# Teensy_PCB.net
KiCad netlist of a schematic drawn in EAGLE
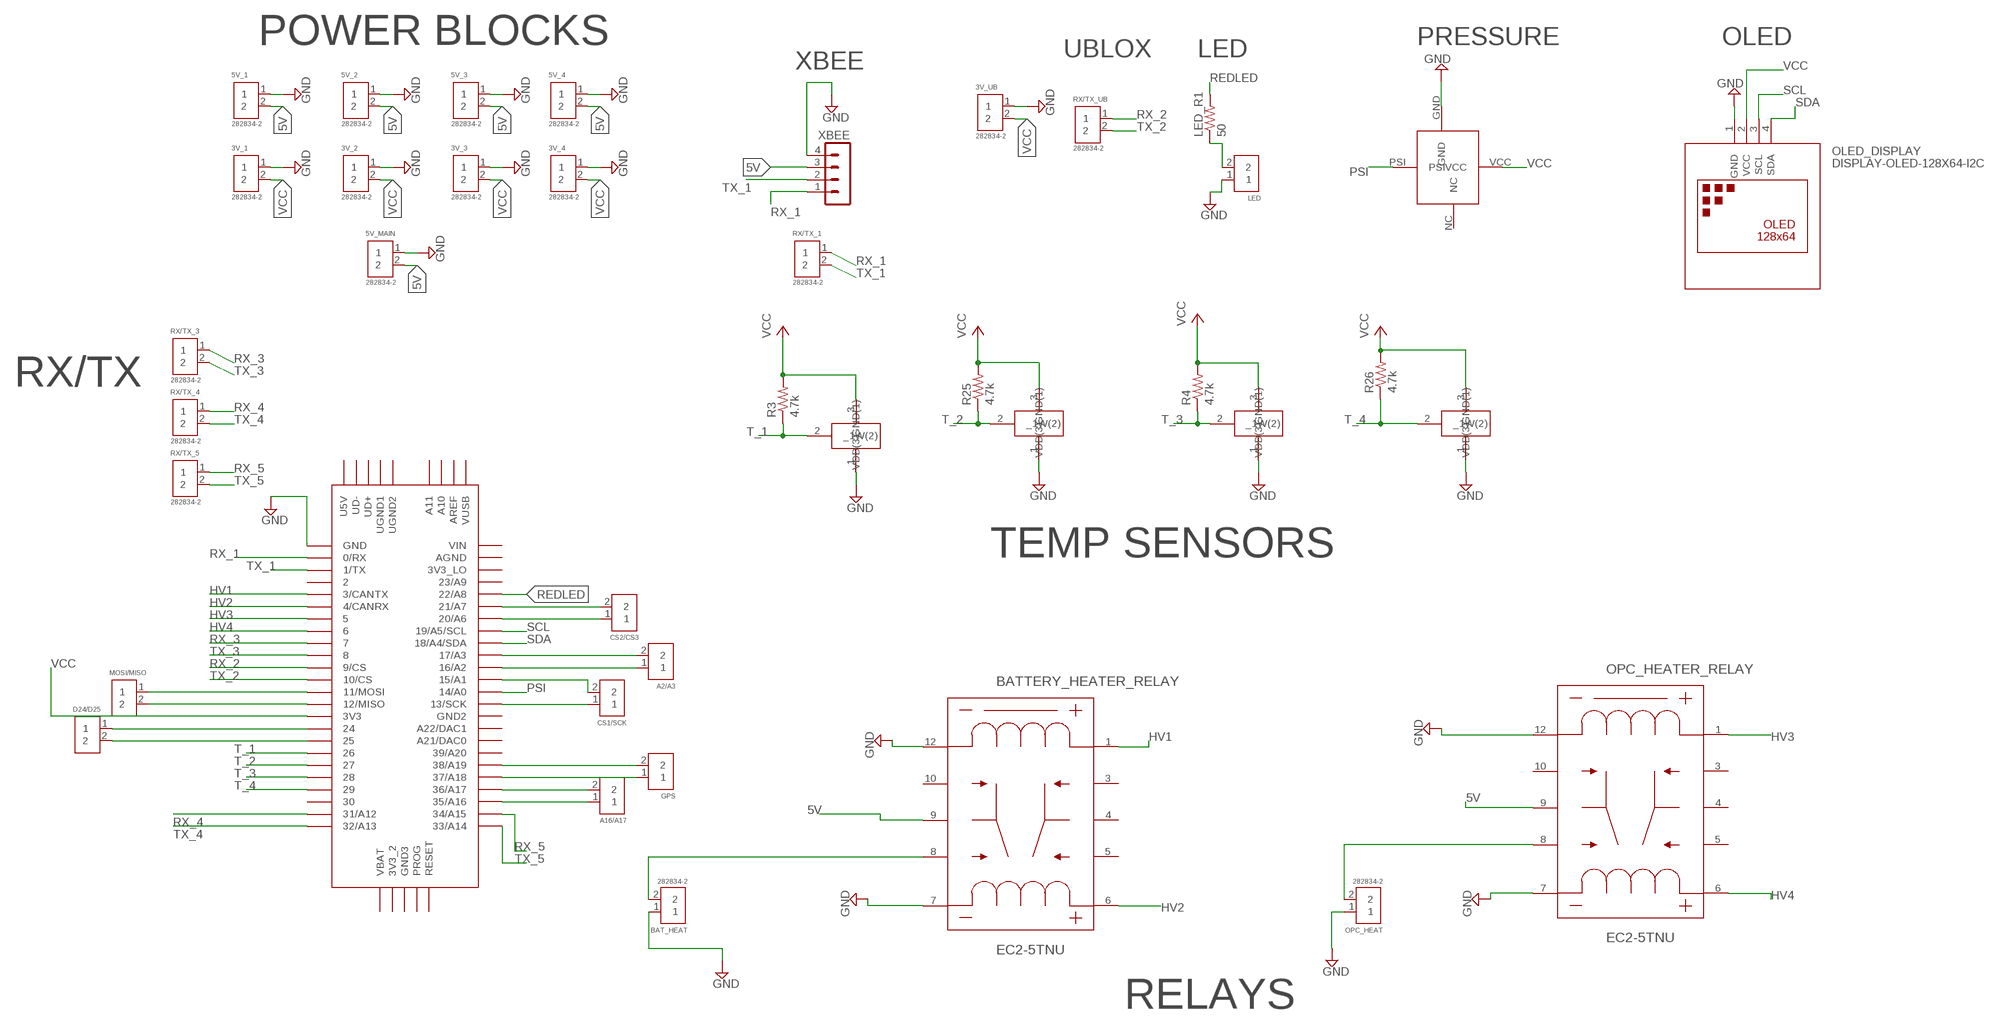
[diagram p0: schematic, sheet 1]

(export (version "E")
  (design (tool "Eeschema 10.0.6"))
  (components
    (comp (ref "3V_1")
      (value "282834-2")
      (footprint "eagle-import:CONN_282834-2")
      (fields (field (name "DIGI-KEY_PART_NUMBER") "A98333-ND") (field (name "MF") "TE Connectivity"))
      (libsource (lib "eagle-import") (part "282834-2"))
    )
    (comp (ref "3V_2")
      (value "282834-2")
      (footprint "eagle-import:CONN_282834-2")
      (fields (field (name "DIGI-KEY_PART_NUMBER") "A98333-ND") (field (name "MF") "TE Connectivity"))
      (libsource (lib "eagle-import") (part "282834-2"))
    )
    (comp (ref "3V_3")
      (value "282834-2")
      (footprint "eagle-import:CONN_282834-2")
      (fields (field (name "DIGI-KEY_PART_NUMBER") "A98333-ND") (field (name "MF") "TE Connectivity"))
      (libsource (lib "eagle-import") (part "282834-2"))
    )
    (comp (ref "3V_4")
      (value "282834-2")
      (footprint "eagle-import:CONN_282834-2")
      (fields (field (name "DIGI-KEY_PART_NUMBER") "A98333-ND") (field (name "MF") "TE Connectivity"))
      (libsource (lib "eagle-import") (part "282834-2"))
    )
    (comp (ref "3V_UB")
      (value "282834-2")
      (footprint "eagle-import:CONN_282834-2")
      (fields (field (name "DIGI-KEY_PART_NUMBER") "A98333-ND") (field (name "MF") "TE Connectivity"))
      (libsource (lib "eagle-import") (part "282834-2"))
    )
    (comp (ref "5V_1")
      (value "282834-2")
      (footprint "eagle-import:CONN_282834-2")
      (fields (field (name "DIGI-KEY_PART_NUMBER") "A98333-ND") (field (name "MF") "TE Connectivity"))
      (libsource (lib "eagle-import") (part "282834-2"))
    )
    (comp (ref "5V_2")
      (value "282834-2")
      (footprint "eagle-import:CONN_282834-2")
      (fields (field (name "DIGI-KEY_PART_NUMBER") "A98333-ND") (field (name "MF") "TE Connectivity"))
      (libsource (lib "eagle-import") (part "282834-2"))
    )
    (comp (ref "5V_3")
      (value "282834-2")
      (footprint "eagle-import:CONN_282834-2")
      (fields (field (name "DIGI-KEY_PART_NUMBER") "A98333-ND") (field (name "MF") "TE Connectivity"))
      (libsource (lib "eagle-import") (part "282834-2"))
    )
    (comp (ref "5V_4")
      (value "282834-2")
      (footprint "eagle-import:CONN_282834-2")
      (fields (field (name "DIGI-KEY_PART_NUMBER") "A98333-ND") (field (name "MF") "TE Connectivity"))
      (libsource (lib "eagle-import") (part "282834-2"))
    )
    (comp (ref "5V_MAIN")
      (value "282834-2")
      (footprint "eagle-import:CONN_282834-2")
      (fields (field (name "DIGI-KEY_PART_NUMBER") "A98333-ND") (field (name "MF") "TE Connectivity"))
      (libsource (lib "eagle-import") (part "282834-2"))
    )
    (comp (ref "A2/A3")
      (value "282834-2")
      (footprint "eagle-import:CONN_282834-2")
      (fields (field (name "DIGI-KEY_PART_NUMBER") "A98333-ND") (field (name "MF") "TE Connectivity"))
      (libsource (lib "eagle-import") (part "282834-2"))
    )
    (comp (ref "A16/A17")
      (value "282834-2")
      (footprint "eagle-import:CONN_282834-2")
      (fields (field (name "DIGI-KEY_PART_NUMBER") "A98333-ND") (field (name "MF") "TE Connectivity"))
      (libsource (lib "eagle-import") (part "282834-2"))
    )
    (comp (ref "BATTERY_HEATER_RELAY")
      (value "EC2-5TNU")
      (footprint "eagle-import:EC2TNU")
      (fields (field (name "MANUFACTURER_PART_NUMBER") "EC25TNU"))
      (libsource (lib "eagle-import") (part "EC2-5TNU"))
    )
    (comp (ref "BAT_HEAT")
      (value "282834-2")
      (footprint "eagle-import:CONN_282834-2")
      (fields (field (name "DIGI-KEY_PART_NUMBER") "A98333-ND") (field (name "MF") "TE Connectivity"))
      (libsource (lib "eagle-import") (part "282834-2"))
    )
    (comp (ref "CS1/SCK")
      (value "282834-2")
      (footprint "eagle-import:CONN_282834-2")
      (fields (field (name "DIGI-KEY_PART_NUMBER") "A98333-ND") (field (name "MF") "TE Connectivity"))
      (libsource (lib "eagle-import") (part "282834-2"))
    )
    (comp (ref "CS2/CS3")
      (value "282834-2")
      (footprint "eagle-import:CONN_282834-2")
      (fields (field (name "DIGI-KEY_PART_NUMBER") "A98333-ND") (field (name "MF") "TE Connectivity"))
      (libsource (lib "eagle-import") (part "282834-2"))
    )
    (comp (ref "D24/D25")
      (value "282834-2")
      (footprint "eagle-import:CONN_282834-2")
      (fields (field (name "DIGI-KEY_PART_NUMBER") "A98333-ND") (field (name "MF") "TE Connectivity"))
      (libsource (lib "eagle-import") (part "282834-2"))
    )
    (comp (ref "GPS")
      (value "282834-2")
      (footprint "eagle-import:CONN_282834-2")
      (fields (field (name "DIGI-KEY_PART_NUMBER") "A98333-ND") (field (name "MF") "TE Connectivity"))
      (libsource (lib "eagle-import") (part "282834-2"))
    )
    (comp (ref "LED")
      (value "282834-2")
      (footprint "eagle-import:CONN_282834-2")
      (fields (field (name "DIGI-KEY_PART_NUMBER") "A98333-ND") (field (name "MF") "TE Connectivity"))
      (libsource (lib "eagle-import") (part "282834-2"))
    )
    (comp (ref "LED_R1")
      (value "50")
      (footprint "eagle-import:0204_7")
      (libsource (lib "eagle-import") (part "R-US_0204/7"))
    )
    (comp (ref "MOSI/MISO")
      (value "282834-2")
      (footprint "eagle-import:CONN_282834-2")
      (fields (field (name "DIGI-KEY_PART_NUMBER") "A98333-ND") (field (name "MF") "TE Connectivity"))
      (libsource (lib "eagle-import") (part "282834-2"))
    )
    (comp (ref "OLED_DISPLAY")
      (value "DISPLAY-OLED-128X64-I2C")
      (footprint "eagle-import:DISPLAY-OLED-128X64-I2C")
      (libsource (lib "eagle-import") (part "DISPLAY-OLED-128X64-I2C"))
    )
    (comp (ref "OPC_HEAT")
      (value "282834-2")
      (footprint "eagle-import:CONN_282834-2")
      (fields (field (name "DIGI-KEY_PART_NUMBER") "A98333-ND") (field (name "MF") "TE Connectivity"))
      (libsource (lib "eagle-import") (part "282834-2"))
    )
    (comp (ref "OPC_HEATER_RELAY")
      (value "EC2-5TNU")
      (footprint "eagle-import:EC2TNU")
      (fields (field (name "MANUFACTURER_PART_NUMBER") "EC25TNU"))
      (libsource (lib "eagle-import") (part "EC2-5TNU"))
    )
    (comp (ref "PRESSURE_SENSOR")
      (value "SSCSANN015PAAA5")
      (footprint "eagle-import:SSCSANN015PAAA5")
      (libsource (lib "eagle-import") (part "SSCSANN015PAAA5"))
    )
    (comp (ref "R3")
      (value "4.7k")
      (footprint "eagle-import:0204_7")
      (libsource (lib "eagle-import") (part "R-US_0204/7"))
    )
    (comp (ref "R4")
      (value "4.7k")
      (footprint "eagle-import:0204_7")
      (libsource (lib "eagle-import") (part "R-US_0204/7"))
    )
    (comp (ref "R25")
      (value "4.7k")
      (footprint "eagle-import:0204_7")
      (libsource (lib "eagle-import") (part "R-US_0204/7"))
    )
    (comp (ref "R26")
      (value "4.7k")
      (footprint "eagle-import:0204_7")
      (libsource (lib "eagle-import") (part "R-US_0204/7"))
    )
    (comp (ref "RX/TX_1")
      (value "282834-2")
      (footprint "eagle-import:CONN_282834-2")
      (fields (field (name "DIGI-KEY_PART_NUMBER") "A98333-ND") (field (name "MF") "TE Connectivity"))
      (libsource (lib "eagle-import") (part "282834-2"))
    )
    (comp (ref "RX/TX_3")
      (value "282834-2")
      (footprint "eagle-import:CONN_282834-2")
      (fields (field (name "DIGI-KEY_PART_NUMBER") "A98333-ND") (field (name "MF") "TE Connectivity"))
      (libsource (lib "eagle-import") (part "282834-2"))
    )
    (comp (ref "RX/TX_4")
      (value "282834-2")
      (footprint "eagle-import:CONN_282834-2")
      (fields (field (name "DIGI-KEY_PART_NUMBER") "A98333-ND") (field (name "MF") "TE Connectivity"))
      (libsource (lib "eagle-import") (part "282834-2"))
    )
    (comp (ref "RX/TX_5")
      (value "282834-2")
      (footprint "eagle-import:CONN_282834-2")
      (fields (field (name "DIGI-KEY_PART_NUMBER") "A98333-ND") (field (name "MF") "TE Connectivity"))
      (libsource (lib "eagle-import") (part "282834-2"))
    )
    (comp (ref "RX/TX_UB")
      (value "282834-2")
      (footprint "eagle-import:CONN_282834-2")
      (fields (field (name "DIGI-KEY_PART_NUMBER") "A98333-ND") (field (name "MF") "TE Connectivity"))
      (libsource (lib "eagle-import") (part "282834-2"))
    )
    (comp (ref "TEMP_1")
      (value "DS18B20.2")
      (footprint "eagle-import:TO92-")
      (libsource (lib "eagle-import") (part "DS18B20.2"))
    )
    (comp (ref "TEMP_2")
      (value "DS18B20.2")
      (footprint "eagle-import:TO92-")
      (libsource (lib "eagle-import") (part "DS18B20.2"))
    )
    (comp (ref "TEMP_3")
      (value "DS18B20.2")
      (footprint "eagle-import:TO92-")
      (libsource (lib "eagle-import") (part "DS18B20.2"))
    )
    (comp (ref "TEMP_4")
      (value "DS18B20.2")
      (footprint "eagle-import:TO92-")
      (libsource (lib "eagle-import") (part "DS18B20.2"))
    )
    (comp (ref "U$1")
      (value "TEENSY_3.5/3.6")
      (footprint "eagle-import:TEENSY_3.5_3.6")
      (libsource (lib "eagle-import") (part "TEENSY_3.5/3.6"))
    )
    (comp (ref "XBEE")
      (value "MA04-1")
      (footprint "eagle-import:MA04-1")
      (libsource (lib "eagle-import") (part "MA04-1"))
    )
  )
  (nets
    (net (code "1") (name "/HV1") (class "Default")
      (node (ref "BATTERY_HEATER_RELAY") (pin "1") (pinfunction "1_1") (pintype "passive"))
      (node (ref "U$1") (pin "3/CANTX") (pinfunction "3/CANTX_3/CANTX") (pintype "bidirectional"))
    )
    (net (code "2") (name "/HV2") (class "Default")
      (node (ref "BATTERY_HEATER_RELAY") (pin "6") (pinfunction "5_6") (pintype "passive"))
      (node (ref "U$1") (pin "4/CANRX") (pinfunction "4/CANRX_4/CANRX") (pintype "bidirectional"))
    )
    (net (code "3") (name "/HV3") (class "Default")
      (node (ref "OPC_HEATER_RELAY") (pin "1") (pinfunction "1_1") (pintype "passive"))
      (node (ref "U$1") (pin "5") (pinfunction "5_5") (pintype "bidirectional"))
    )
    (net (code "4") (name "/HV4") (class "Default")
      (node (ref "OPC_HEATER_RELAY") (pin "6") (pinfunction "5_6") (pintype "passive"))
      (node (ref "U$1") (pin "6") (pinfunction "6_6") (pintype "bidirectional"))
    )
    (net (code "5") (name "/PSI") (class "Default")
      (node (ref "PRESSURE_SENSOR") (pin "PSI") (pinfunction "PSI_PSI") (pintype "bidirectional"))
      (node (ref "U$1") (pin "14/A0") (pinfunction "14/A0_14/A0") (pintype "bidirectional"))
    )
    (net (code "6") (name "/RX_1") (class "Default")
      (node (ref "RX/TX_1") (pin "1") (pinfunction "1_1") (pintype "passive"))
      (node (ref "U$1") (pin "0/RX") (pinfunction "0/RX_0/RX") (pintype "bidirectional"))
      (node (ref "XBEE") (pin "1") (pinfunction "1_1") (pintype "passive"))
    )
    (net (code "7") (name "/RX_2") (class "Default")
      (node (ref "RX/TX_UB") (pin "1") (pinfunction "1_1") (pintype "passive"))
      (node (ref "U$1") (pin "9/CS") (pinfunction "9/CS_9/CS") (pintype "bidirectional"))
    )
    (net (code "8") (name "/RX_3") (class "Default")
      (node (ref "RX/TX_3") (pin "1") (pinfunction "1_1") (pintype "passive"))
      (node (ref "U$1") (pin "7") (pinfunction "7_7") (pintype "bidirectional"))
    )
    (net (code "9") (name "/RX_4") (class "Default")
      (node (ref "RX/TX_4") (pin "1") (pinfunction "1_1") (pintype "passive"))
      (node (ref "U$1") (pin "31/A12") (pinfunction "31/A12_31/A12") (pintype "bidirectional"))
    )
    (net (code "10") (name "/RX_5") (class "Default")
      (node (ref "RX/TX_5") (pin "1") (pinfunction "1_1") (pintype "passive"))
      (node (ref "U$1") (pin "34/A15") (pinfunction "34/A15_34/A15") (pintype "bidirectional"))
    )
    (net (code "11") (name "/SCL") (class "Default")
      (node (ref "OLED_DISPLAY") (pin "3") (pinfunction "SCL_3") (pintype "bidirectional"))
      (node (ref "U$1") (pin "19/A5/SCL") (pinfunction "19/A5/SCL_19/A5/SCL") (pintype "bidirectional"))
    )
    (net (code "12") (name "/SDA") (class "Default")
      (node (ref "OLED_DISPLAY") (pin "4") (pinfunction "SDA_4") (pintype "bidirectional"))
      (node (ref "U$1") (pin "18/A4/SDA") (pinfunction "18/A4/SDA_18/A4/SDA") (pintype "bidirectional"))
    )
    (net (code "13") (name "/TX_1") (class "Default")
      (node (ref "RX/TX_1") (pin "2") (pinfunction "2_2") (pintype "passive"))
      (node (ref "U$1") (pin "1/TX") (pinfunction "1/TX_1/TX") (pintype "bidirectional"))
      (node (ref "XBEE") (pin "2") (pinfunction "2_2") (pintype "passive"))
    )
    (net (code "14") (name "/TX_2") (class "Default")
      (node (ref "RX/TX_UB") (pin "2") (pinfunction "2_2") (pintype "passive"))
      (node (ref "U$1") (pin "10/CS") (pinfunction "10/CS_10/CS") (pintype "bidirectional"))
    )
    (net (code "15") (name "/TX_3") (class "Default")
      (node (ref "RX/TX_3") (pin "2") (pinfunction "2_2") (pintype "passive"))
      (node (ref "U$1") (pin "8") (pinfunction "8_8") (pintype "bidirectional"))
    )
    (net (code "16") (name "/TX_4") (class "Default")
      (node (ref "RX/TX_4") (pin "2") (pinfunction "2_2") (pintype "passive"))
      (node (ref "U$1") (pin "32/A13") (pinfunction "32/A13_32/A13") (pintype "bidirectional"))
    )
    (net (code "17") (name "/TX_5") (class "Default")
      (node (ref "RX/TX_5") (pin "2") (pinfunction "2_2") (pintype "passive"))
      (node (ref "U$1") (pin "33/A14") (pinfunction "33/A14_33/A14") (pintype "bidirectional"))
    )
    (net (code "18") (name "/T_1") (class "Default")
      (node (ref "R3") (pin "1") (pinfunction "1_1") (pintype "passive"))
      (node (ref "TEMP_1") (pin "2") (pinfunction "_1W(2)_2") (pintype "bidirectional"))
      (node (ref "U$1") (pin "26") (pinfunction "26_26") (pintype "bidirectional"))
    )
    (net (code "19") (name "/T_2") (class "Default")
      (node (ref "R25") (pin "1") (pinfunction "1_1") (pintype "passive"))
      (node (ref "TEMP_2") (pin "2") (pinfunction "_1W(2)_2") (pintype "bidirectional"))
      (node (ref "U$1") (pin "27") (pinfunction "27_27") (pintype "bidirectional"))
    )
    (net (code "20") (name "/T_3") (class "Default")
      (node (ref "R4") (pin "1") (pinfunction "1_1") (pintype "passive"))
      (node (ref "TEMP_3") (pin "2") (pinfunction "_1W(2)_2") (pintype "bidirectional"))
      (node (ref "U$1") (pin "28") (pinfunction "28_28") (pintype "bidirectional"))
    )
    (net (code "21") (name "/T_4") (class "Default")
      (node (ref "R26") (pin "1") (pinfunction "1_1") (pintype "passive"))
      (node (ref "TEMP_4") (pin "2") (pinfunction "_1W(2)_2") (pintype "bidirectional"))
      (node (ref "U$1") (pin "29") (pinfunction "29_29") (pintype "bidirectional"))
    )
    (net (code "22") (name "5V") (class "Default")
      (node (ref "5V_1") (pin "2") (pinfunction "2_2") (pintype "passive"))
      (node (ref "5V_2") (pin "2") (pinfunction "2_2") (pintype "passive"))
      (node (ref "5V_3") (pin "2") (pinfunction "2_2") (pintype "passive"))
      (node (ref "5V_4") (pin "2") (pinfunction "2_2") (pintype "passive"))
      (node (ref "5V_MAIN") (pin "2") (pinfunction "2_2") (pintype "passive"))
      (node (ref "BATTERY_HEATER_RELAY") (pin "9") (pinfunction "8_9") (pintype "passive"))
      (node (ref "OPC_HEATER_RELAY") (pin "9") (pinfunction "8_9") (pintype "passive"))
      (node (ref "XBEE") (pin "3") (pinfunction "3_3") (pintype "passive"))
    )
    (net (code "23") (name "GND") (class "Default")
      (node (ref "3V_1") (pin "1") (pinfunction "1_1") (pintype "passive"))
      (node (ref "3V_2") (pin "1") (pinfunction "1_1") (pintype "passive"))
      (node (ref "3V_3") (pin "1") (pinfunction "1_1") (pintype "passive"))
      (node (ref "3V_4") (pin "1") (pinfunction "1_1") (pintype "passive"))
      (node (ref "3V_UB") (pin "1") (pinfunction "1_1") (pintype "passive"))
      (node (ref "5V_1") (pin "1") (pinfunction "1_1") (pintype "passive"))
      (node (ref "5V_2") (pin "1") (pinfunction "1_1") (pintype "passive"))
      (node (ref "5V_3") (pin "1") (pinfunction "1_1") (pintype "passive"))
      (node (ref "5V_4") (pin "1") (pinfunction "1_1") (pintype "passive"))
      (node (ref "5V_MAIN") (pin "1") (pinfunction "1_1") (pintype "passive"))
      (node (ref "BATTERY_HEATER_RELAY") (pin "12") (pinfunction "10_12") (pintype "passive"))
      (node (ref "BATTERY_HEATER_RELAY") (pin "7") (pinfunction "6_7") (pintype "passive"))
      (node (ref "BAT_HEAT") (pin "1") (pinfunction "1_1") (pintype "passive"))
      (node (ref "LED") (pin "1") (pinfunction "1_1") (pintype "passive"))
      (node (ref "OLED_DISPLAY") (pin "1") (pinfunction "GND_1") (pintype "power_in"))
      (node (ref "OPC_HEAT") (pin "1") (pinfunction "1_1") (pintype "passive"))
      (node (ref "OPC_HEATER_RELAY") (pin "12") (pinfunction "10_12") (pintype "passive"))
      (node (ref "OPC_HEATER_RELAY") (pin "7") (pinfunction "6_7") (pintype "passive"))
      (node (ref "PRESSURE_SENSOR") (pin "GND") (pinfunction "GND_GND") (pintype "bidirectional"))
      (node (ref "TEMP_1") (pin "1") (pinfunction "GND(1)_1") (pintype "bidirectional"))
      (node (ref "TEMP_2") (pin "1") (pinfunction "GND(1)_1") (pintype "bidirectional"))
      (node (ref "TEMP_3") (pin "1") (pinfunction "GND(1)_1") (pintype "bidirectional"))
      (node (ref "TEMP_4") (pin "1") (pinfunction "GND(1)_1") (pintype "bidirectional"))
      (node (ref "U$1") (pin "GND") (pinfunction "GND_GND") (pintype "bidirectional"))
      (node (ref "XBEE") (pin "4") (pinfunction "4_4") (pintype "passive"))
    )
    (net (code "24") (name "Net-(A2/A3-Pad1)") (class "Default")
      (node (ref "A2/A3") (pin "1") (pinfunction "1_1") (pintype "passive"))
      (node (ref "U$1") (pin "16/A2") (pinfunction "16/A2_16/A2") (pintype "bidirectional"))
    )
    (net (code "25") (name "Net-(A2/A3-Pad2)") (class "Default")
      (node (ref "A2/A3") (pin "2") (pinfunction "2_2") (pintype "passive"))
      (node (ref "U$1") (pin "17/A3") (pinfunction "17/A3_17/A3") (pintype "bidirectional"))
    )
    (net (code "26") (name "Net-(A16/A17-Pad1)") (class "Default")
      (node (ref "A16/A17") (pin "1") (pinfunction "1_1") (pintype "passive"))
      (node (ref "U$1") (pin "35/A16") (pinfunction "35/A16_35/A16") (pintype "bidirectional"))
    )
    (net (code "27") (name "Net-(A16/A17-Pad2)") (class "Default")
      (node (ref "A16/A17") (pin "2") (pinfunction "2_2") (pintype "passive"))
      (node (ref "U$1") (pin "36/A17") (pinfunction "36/A17_36/A17") (pintype "bidirectional"))
    )
    (net (code "28") (name "Net-(BATTERY_HEATER_RELAY-7)") (class "Default")
      (node (ref "BATTERY_HEATER_RELAY") (pin "8") (pinfunction "7_8") (pintype "passive"))
      (node (ref "BAT_HEAT") (pin "2") (pinfunction "2_2") (pintype "passive"))
    )
    (net (code "29") (name "Net-(CS1/SCK-Pad1)") (class "Default")
      (node (ref "CS1/SCK") (pin "1") (pinfunction "1_1") (pintype "passive"))
      (node (ref "U$1") (pin "13/SCK") (pinfunction "13/SCK_13/SCK") (pintype "bidirectional"))
    )
    (net (code "30") (name "Net-(CS1/SCK-Pad2)") (class "Default")
      (node (ref "CS1/SCK") (pin "2") (pinfunction "2_2") (pintype "passive"))
      (node (ref "U$1") (pin "15/A1") (pinfunction "15/A1_15/A1") (pintype "bidirectional"))
    )
    (net (code "31") (name "Net-(CS2/CS3-Pad1)") (class "Default")
      (node (ref "CS2/CS3") (pin "1") (pinfunction "1_1") (pintype "passive"))
      (node (ref "U$1") (pin "20/A6") (pinfunction "20/A6_20/A6") (pintype "bidirectional"))
    )
    (net (code "32") (name "Net-(CS2/CS3-Pad2)") (class "Default")
      (node (ref "CS2/CS3") (pin "2") (pinfunction "2_2") (pintype "passive"))
      (node (ref "U$1") (pin "21/A7") (pinfunction "21/A7_21/A7") (pintype "bidirectional"))
    )
    (net (code "33") (name "Net-(D24/D25-Pad1)") (class "Default")
      (node (ref "D24/D25") (pin "1") (pinfunction "1_1") (pintype "passive"))
      (node (ref "U$1") (pin "24") (pinfunction "24_24") (pintype "bidirectional"))
    )
    (net (code "34") (name "Net-(D24/D25-Pad2)") (class "Default")
      (node (ref "D24/D25") (pin "2") (pinfunction "2_2") (pintype "passive"))
      (node (ref "U$1") (pin "25") (pinfunction "25_25") (pintype "bidirectional"))
    )
    (net (code "35") (name "Net-(GPS-Pad1)") (class "Default")
      (node (ref "GPS") (pin "1") (pinfunction "1_1") (pintype "passive"))
      (node (ref "U$1") (pin "37/A18") (pinfunction "37/A18_37/A18") (pintype "bidirectional"))
    )
    (net (code "36") (name "Net-(GPS-Pad2)") (class "Default")
      (node (ref "GPS") (pin "2") (pinfunction "2_2") (pintype "passive"))
      (node (ref "U$1") (pin "38/A19") (pinfunction "38/A19_38/A19") (pintype "bidirectional"))
    )
    (net (code "37") (name "Net-(LED-Pad2)") (class "Default")
      (node (ref "LED") (pin "2") (pinfunction "2_2") (pintype "passive"))
      (node (ref "LED_R1") (pin "1") (pinfunction "1_1") (pintype "passive"))
    )
    (net (code "38") (name "Net-(MOSI/MISO-Pad1)") (class "Default")
      (node (ref "MOSI/MISO") (pin "1") (pinfunction "1_1") (pintype "passive"))
      (node (ref "U$1") (pin "11/MOSI") (pinfunction "11/MOSI_11/MOSI") (pintype "bidirectional"))
    )
    (net (code "39") (name "Net-(MOSI/MISO-Pad2)") (class "Default")
      (node (ref "MOSI/MISO") (pin "2") (pinfunction "2_2") (pintype "passive"))
      (node (ref "U$1") (pin "12/MISO") (pinfunction "12/MISO_12/MISO") (pintype "bidirectional"))
    )
    (net (code "40") (name "Net-(OPC_HEATER_RELAY-7)") (class "Default")
      (node (ref "OPC_HEAT") (pin "2") (pinfunction "2_2") (pintype "passive"))
      (node (ref "OPC_HEATER_RELAY") (pin "8") (pinfunction "7_8") (pintype "passive"))
    )
    (net (code "41") (name "REDLED") (class "Default")
      (node (ref "LED_R1") (pin "2") (pinfunction "2_2") (pintype "passive"))
      (node (ref "U$1") (pin "22/A8") (pinfunction "22/A8_22/A8") (pintype "bidirectional"))
    )
    (net (code "42") (name "VCC") (class "Default")
      (node (ref "3V_1") (pin "2") (pinfunction "2_2") (pintype "passive"))
      (node (ref "3V_2") (pin "2") (pinfunction "2_2") (pintype "passive"))
      (node (ref "3V_3") (pin "2") (pinfunction "2_2") (pintype "passive"))
      (node (ref "3V_4") (pin "2") (pinfunction "2_2") (pintype "passive"))
      (node (ref "3V_UB") (pin "2") (pinfunction "2_2") (pintype "passive"))
      (node (ref "OLED_DISPLAY") (pin "2") (pinfunction "VCC_2") (pintype "power_in"))
      (node (ref "PRESSURE_SENSOR") (pin "VCC") (pinfunction "VCC_VCC") (pintype "bidirectional"))
      (node (ref "R25") (pin "2") (pinfunction "2_2") (pintype "passive"))
      (node (ref "R26") (pin "2") (pinfunction "2_2") (pintype "passive"))
      (node (ref "R3") (pin "2") (pinfunction "2_2") (pintype "passive"))
      (node (ref "R4") (pin "2") (pinfunction "2_2") (pintype "passive"))
      (node (ref "TEMP_1") (pin "3") (pinfunction "VDD(3)_3") (pintype "bidirectional"))
      (node (ref "TEMP_2") (pin "3") (pinfunction "VDD(3)_3") (pintype "bidirectional"))
      (node (ref "TEMP_3") (pin "3") (pinfunction "VDD(3)_3") (pintype "bidirectional"))
      (node (ref "TEMP_4") (pin "3") (pinfunction "VDD(3)_3") (pintype "bidirectional"))
      (node (ref "U$1") (pin "3V3") (pinfunction "3V3_3V3") (pintype "bidirectional"))
    )
    (net (code "43") (name "unconnected-(BATTERY_HEATER_RELAY-2-Pad3)") (class "Default")
      (node (ref "BATTERY_HEATER_RELAY") (pin "3") (pinfunction "2_3") (pintype "passive"))
    )
    (net (code "44") (name "unconnected-(BATTERY_HEATER_RELAY-3-Pad4)") (class "Default")
      (node (ref "BATTERY_HEATER_RELAY") (pin "4") (pinfunction "3_4") (pintype "passive"))
    )
    (net (code "45") (name "unconnected-(BATTERY_HEATER_RELAY-4-Pad5)") (class "Default")
      (node (ref "BATTERY_HEATER_RELAY") (pin "5") (pinfunction "4_5") (pintype "passive"))
    )
    (net (code "46") (name "unconnected-(BATTERY_HEATER_RELAY-9-Pad10)") (class "Default")
      (node (ref "BATTERY_HEATER_RELAY") (pin "10") (pinfunction "9_10") (pintype "passive"))
    )
    (net (code "47") (name "unconnected-(OPC_HEATER_RELAY-2-Pad3)") (class "Default")
      (node (ref "OPC_HEATER_RELAY") (pin "3") (pinfunction "2_3") (pintype "passive"))
    )
    (net (code "48") (name "unconnected-(OPC_HEATER_RELAY-3-Pad4)") (class "Default")
      (node (ref "OPC_HEATER_RELAY") (pin "4") (pinfunction "3_4") (pintype "passive"))
    )
    (net (code "49") (name "unconnected-(OPC_HEATER_RELAY-4-Pad5)") (class "Default")
      (node (ref "OPC_HEATER_RELAY") (pin "5") (pinfunction "4_5") (pintype "passive"))
    )
    (net (code "50") (name "unconnected-(OPC_HEATER_RELAY-9-Pad10)") (class "Default")
      (node (ref "OPC_HEATER_RELAY") (pin "10") (pinfunction "9_10") (pintype "passive"))
    )
    (net (code "51") (name "unconnected-(PRESSURE_SENSOR-PadNC)") (class "Default")
      (node (ref "PRESSURE_SENSOR") (pin "NC") (pinfunction "NC_NC") (pintype "bidirectional"))
    )
    (net (code "52") (name "unconnected-(U$1-A21{slash}DAC0-Pad21{slash}DAC0)") (class "Default")
      (node (ref "U$1") (pin "21/DAC0") (pinfunction "A21/DAC0_21/DAC0") (pintype "bidirectional"))
    )
    (net (code "53") (name "unconnected-(U$1-Pad2)") (class "Default")
      (node (ref "U$1") (pin "2") (pinfunction "2_2") (pintype "bidirectional"))
    )
    (net (code "54") (name "unconnected-(U$1-Pad3V3_2)") (class "Default")
      (node (ref "U$1") (pin "3V3_2") (pinfunction "3V3_2_3V3_2") (pintype "bidirectional"))
    )
    (net (code "55") (name "unconnected-(U$1-Pad3V3_LO)") (class "Default")
      (node (ref "U$1") (pin "3V3_LO") (pinfunction "3V3_LO_3V3_LO") (pintype "bidirectional"))
    )
    (net (code "56") (name "unconnected-(U$1-Pad23{slash}A9)") (class "Default")
      (node (ref "U$1") (pin "23/A9") (pinfunction "23/A9_23/A9") (pintype "bidirectional"))
    )
    (net (code "57") (name "unconnected-(U$1-Pad30)") (class "Default")
      (node (ref "U$1") (pin "30") (pinfunction "30_30") (pintype "bidirectional"))
    )
    (net (code "58") (name "unconnected-(U$1-Pad39{slash}A20)") (class "Default")
      (node (ref "U$1") (pin "39/A20") (pinfunction "39/A20_39/A20") (pintype "bidirectional"))
    )
    (net (code "59") (name "unconnected-(U$1-PadA10)") (class "Default")
      (node (ref "U$1") (pin "A10") (pinfunction "A10_A10") (pintype "bidirectional"))
    )
    (net (code "60") (name "unconnected-(U$1-PadA11)") (class "Default")
      (node (ref "U$1") (pin "A11") (pinfunction "A11_A11") (pintype "bidirectional"))
    )
    (net (code "61") (name "unconnected-(U$1-PadA22{slash}DAC1)") (class "Default")
      (node (ref "U$1") (pin "A22/DAC1") (pinfunction "A22/DAC1_A22/DAC1") (pintype "bidirectional"))
    )
    (net (code "62") (name "unconnected-(U$1-PadAGND)") (class "Default")
      (node (ref "U$1") (pin "AGND") (pinfunction "AGND_AGND") (pintype "bidirectional"))
    )
    (net (code "63") (name "unconnected-(U$1-PadAREF)") (class "Default")
      (node (ref "U$1") (pin "AREF") (pinfunction "AREF_AREF") (pintype "bidirectional"))
    )
    (net (code "64") (name "unconnected-(U$1-PadGND2)") (class "Default")
      (node (ref "U$1") (pin "GND2") (pinfunction "GND2_GND2") (pintype "bidirectional"))
    )
    (net (code "65") (name "unconnected-(U$1-PadGND3)") (class "Default")
      (node (ref "U$1") (pin "GND3") (pinfunction "GND3_GND3") (pintype "bidirectional"))
    )
    (net (code "66") (name "unconnected-(U$1-PadPROG)") (class "Default")
      (node (ref "U$1") (pin "PROG") (pinfunction "PROG_PROG") (pintype "bidirectional"))
    )
    (net (code "67") (name "unconnected-(U$1-PadRESET)") (class "Default")
      (node (ref "U$1") (pin "RESET") (pinfunction "RESET_RESET") (pintype "bidirectional"))
    )
    (net (code "68") (name "unconnected-(U$1-PadU5V)") (class "Default")
      (node (ref "U$1") (pin "U5V") (pinfunction "U5V_U5V") (pintype "bidirectional"))
    )
    (net (code "69") (name "unconnected-(U$1-PadUD+)") (class "Default")
      (node (ref "U$1") (pin "UD+") (pinfunction "UD+_UD+") (pintype "bidirectional"))
    )
    (net (code "70") (name "unconnected-(U$1-PadUD-)") (class "Default")
      (node (ref "U$1") (pin "UD-") (pinfunction "UD-_UD-") (pintype "bidirectional"))
    )
    (net (code "71") (name "unconnected-(U$1-PadUGND1)") (class "Default")
      (node (ref "U$1") (pin "UGND1") (pinfunction "UGND1_UGND1") (pintype "bidirectional"))
    )
    (net (code "72") (name "unconnected-(U$1-PadUGND2)") (class "Default")
      (node (ref "U$1") (pin "UGND2") (pinfunction "UGND2_UGND2") (pintype "bidirectional"))
    )
    (net (code "73") (name "unconnected-(U$1-PadVBAT)") (class "Default")
      (node (ref "U$1") (pin "VBAT") (pinfunction "VBAT_VBAT") (pintype "bidirectional"))
    )
    (net (code "74") (name "unconnected-(U$1-PadVIN)") (class "Default")
      (node (ref "U$1") (pin "VIN") (pinfunction "VIN_VIN") (pintype "bidirectional"))
    )
    (net (code "75") (name "unconnected-(U$1-PadVUSB)") (class "Default")
      (node (ref "U$1") (pin "VUSB") (pinfunction "VUSB_VUSB") (pintype "bidirectional"))
    )
  )
)
